# nixieklok.net
KiCad netlist of a schematic drawn in Altium Designer
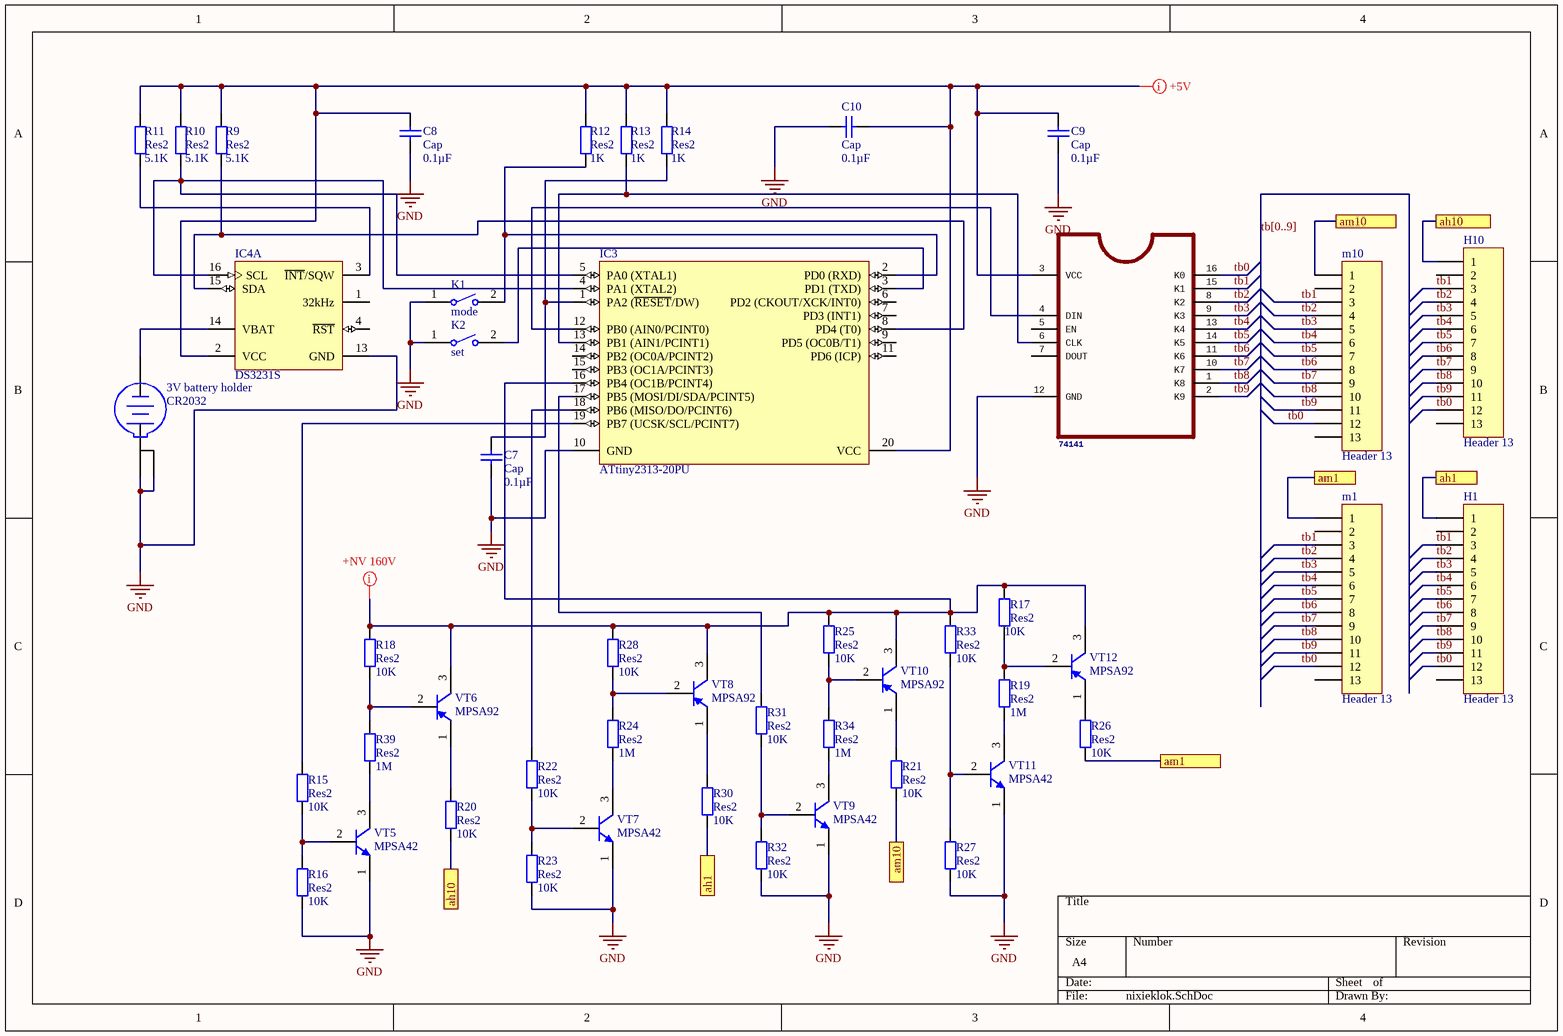
[diagram p0: nixieklok.SchDoc]

(export (version "E")
  (design (tool "Eeschema 10.0.6"))
  (components
    (comp (ref "3V battery holder")
      (value "CR2032")
      (footprint "RENA-HU2032-LF_V")
      (description "Coin Cell Battery Holder, CR2032, Horizontal, -40 to 100 degC, 3-Pin THD, RoHS, Tray")
      (fields (field (name "MANUFACTURER") "Renata"))
      (libsource (lib "Altium Content Vault") (part "BATTERY-HOLDER-COIN-3"))
    )
    (comp (ref "74141")
      (value "NIXIE_DRIVER_V1")
      (footprint "DIP-16")
      (fields (field (name "LIBRARYNAME") "Nixie_Tube_Driver_Altium_Library"))
      (libsource (lib "Nixie_Tube_Driver_Altium_Library") (part "NIXIE_DRIVER_V1"))
    )
    (comp (ref "C7")
      (value "Cap")
      (footprint "RAD-0.3")
      (description "Capacitor")
      (fields (field (name "ALTIUM_VALUE") "0.1µF") (field (name "PUBLISHER") "Altium Limited"))
      (libsource (lib "Miscellaneous Devices") (part "Cap"))
    )
    (comp (ref "C8")
      (value "Cap")
      (footprint "RAD-0.3")
      (description "Capacitor")
      (fields (field (name "ALTIUM_VALUE") "0.1µF") (field (name "PUBLISHER") "Altium Limited"))
      (libsource (lib "Miscellaneous Devices") (part "Cap"))
    )
    (comp (ref "C9")
      (value "Cap")
      (footprint "RAD-0.3")
      (description "Capacitor")
      (fields (field (name "ALTIUM_VALUE") "0.1µF") (field (name "PUBLISHER") "Altium Limited"))
      (libsource (lib "Miscellaneous Devices") (part "Cap"))
    )
    (comp (ref "C10")
      (value "Cap")
      (footprint "RAD-0.3")
      (description "Capacitor")
      (fields (field (name "ALTIUM_VALUE") "0.1µF") (field (name "PUBLISHER") "Altium Limited"))
      (libsource (lib "Miscellaneous Devices") (part "Cap"))
    )
    (comp (ref "H1")
      (value "Header 13")
      (footprint "HDR1X13")
      (description "Header, 13-Pin")
      (fields (field (name "PUBLISHER") "Altium Limited"))
      (libsource (lib "Miscellaneous Connectors") (part "Header 13"))
    )
    (comp (ref "H10")
      (value "Header 13")
      (footprint "HDR1X13")
      (description "Header, 13-Pin")
      (fields (field (name "PUBLISHER") "Altium Limited"))
      (libsource (lib "Miscellaneous Connectors") (part "Header 13"))
    )
    (comp (ref "IC3")
      (value "ATtiny2313-20PU")
      (footprint "20P3")
      (libsource (lib "Altium Content Vault") (part "MC-8B-ATT2313-IL20"))
    )
    (comp (ref "IC4")
      (value "DS3231S")
      (footprint "W16-H2_L")
      (description "Extremely Accurate I2C-Integrated Real-Time Clock/TCXO/Crystal, 16-Pin SO, 0 to 70 degC")
      (libsource (lib "Altium Content Vault") (part "MAX-RTC-16-DS3231S-W16#H2"))
    )
    (comp (ref "K1")
      (value "mode")
      (footprint "TECO-FSMSM-2_V")
      (description "FSMSM Push Button Switch, 50 mA, -35 to 85 degC, 2-Pin SMD, RoHS, Bulk")
      (fields (field (name "MANUFACTURER") "TE Connectivity"))
      (libsource (lib "Altium Content Vault") (part "SW-SPST-2_C"))
    )
    (comp (ref "K2")
      (value "set")
      (footprint "TECO-FSMSM-2_V")
      (description "FSMSM Push Button Switch, 50 mA, -35 to 85 degC, 2-Pin SMD, RoHS, Bulk")
      (fields (field (name "MANUFACTURER") "TE Connectivity"))
      (libsource (lib "Altium Content Vault") (part "SW-SPST-2_C"))
    )
    (comp (ref "m1")
      (value "Header 13")
      (footprint "HDR1X13")
      (description "Header, 13-Pin")
      (fields (field (name "PUBLISHER") "Altium Limited"))
      (libsource (lib "Miscellaneous Connectors") (part "Header 13"))
    )
    (comp (ref "m10")
      (value "Header 13")
      (footprint "HDR1X13")
      (description "Header, 13-Pin")
      (fields (field (name "PUBLISHER") "Altium Limited"))
      (libsource (lib "Miscellaneous Connectors") (part "Header 13"))
    )
    (comp (ref "R9")
      (value "Res2")
      (footprint "AXIAL-0.4")
      (description "Resistor")
      (fields (field (name "ALTIUM_VALUE") "5.1K") (field (name "PUBLISHER") "Altium Limited"))
      (libsource (lib "Miscellaneous Devices") (part "Res2"))
    )
    (comp (ref "R10")
      (value "Res2")
      (footprint "AXIAL-0.4")
      (description "Resistor")
      (fields (field (name "ALTIUM_VALUE") "5.1K") (field (name "PUBLISHER") "Altium Limited"))
      (libsource (lib "Miscellaneous Devices") (part "Res2"))
    )
    (comp (ref "R11")
      (value "Res2")
      (footprint "AXIAL-0.4")
      (description "Resistor")
      (fields (field (name "ALTIUM_VALUE") "5.1K") (field (name "PUBLISHER") "Altium Limited"))
      (libsource (lib "Miscellaneous Devices") (part "Res2"))
    )
    (comp (ref "R12")
      (value "Res2")
      (footprint "AXIAL-0.4")
      (description "Resistor")
      (fields (field (name "ALTIUM_VALUE") "1K") (field (name "PUBLISHER") "Altium Limited"))
      (libsource (lib "Miscellaneous Devices") (part "Res2"))
    )
    (comp (ref "R13")
      (value "Res2")
      (footprint "AXIAL-0.4")
      (description "Resistor")
      (fields (field (name "ALTIUM_VALUE") "1K") (field (name "PUBLISHER") "Altium Limited"))
      (libsource (lib "Miscellaneous Devices") (part "Res2"))
    )
    (comp (ref "R14")
      (value "Res2")
      (footprint "AXIAL-0.4")
      (description "Resistor")
      (fields (field (name "ALTIUM_VALUE") "1K") (field (name "PUBLISHER") "Altium Limited"))
      (libsource (lib "Miscellaneous Devices") (part "Res2"))
    )
    (comp (ref "R15")
      (value "Res2")
      (footprint "AXIAL-0.4")
      (description "Resistor")
      (fields (field (name "ALTIUM_VALUE") "10K") (field (name "PUBLISHER") "Altium Limited"))
      (libsource (lib "Miscellaneous Devices") (part "Res2"))
    )
    (comp (ref "R16")
      (value "Res2")
      (footprint "AXIAL-0.4")
      (description "Resistor")
      (fields (field (name "ALTIUM_VALUE") "10K") (field (name "PUBLISHER") "Altium Limited"))
      (libsource (lib "Miscellaneous Devices") (part "Res2"))
    )
    (comp (ref "R17")
      (value "Res2")
      (footprint "AXIAL-0.4")
      (description "Resistor")
      (fields (field (name "ALTIUM_VALUE") "10K") (field (name "PUBLISHER") "Altium Limited"))
      (libsource (lib "Miscellaneous Devices") (part "Res2"))
    )
    (comp (ref "R18")
      (value "Res2")
      (footprint "AXIAL-0.4")
      (description "Resistor")
      (fields (field (name "ALTIUM_VALUE") "10K") (field (name "PUBLISHER") "Altium Limited"))
      (libsource (lib "Miscellaneous Devices") (part "Res2"))
    )
    (comp (ref "R19")
      (value "Res2")
      (footprint "AXIAL-0.4")
      (description "Resistor")
      (fields (field (name "ALTIUM_VALUE") "1M") (field (name "PUBLISHER") "Altium Limited"))
      (libsource (lib "Miscellaneous Devices") (part "Res2"))
    )
    (comp (ref "R20")
      (value "Res2")
      (footprint "AXIAL-0.4")
      (description "Resistor")
      (fields (field (name "ALTIUM_VALUE") "10K") (field (name "PUBLISHER") "Altium Limited"))
      (libsource (lib "Miscellaneous Devices") (part "Res2"))
    )
    (comp (ref "R21")
      (value "Res2")
      (footprint "AXIAL-0.4")
      (description "Resistor")
      (fields (field (name "ALTIUM_VALUE") "10K") (field (name "PUBLISHER") "Altium Limited"))
      (libsource (lib "Miscellaneous Devices") (part "Res2"))
    )
    (comp (ref "R22")
      (value "Res2")
      (footprint "AXIAL-0.4")
      (description "Resistor")
      (fields (field (name "ALTIUM_VALUE") "10K") (field (name "PUBLISHER") "Altium Limited"))
      (libsource (lib "Miscellaneous Devices") (part "Res2"))
    )
    (comp (ref "R23")
      (value "Res2")
      (footprint "AXIAL-0.4")
      (description "Resistor")
      (fields (field (name "ALTIUM_VALUE") "10K") (field (name "PUBLISHER") "Altium Limited"))
      (libsource (lib "Miscellaneous Devices") (part "Res2"))
    )
    (comp (ref "R24")
      (value "Res2")
      (footprint "AXIAL-0.4")
      (description "Resistor")
      (fields (field (name "ALTIUM_VALUE") "1M") (field (name "PUBLISHER") "Altium Limited"))
      (libsource (lib "Miscellaneous Devices") (part "Res2"))
    )
    (comp (ref "R25")
      (value "Res2")
      (footprint "AXIAL-0.4")
      (description "Resistor")
      (fields (field (name "ALTIUM_VALUE") "10K") (field (name "PUBLISHER") "Altium Limited"))
      (libsource (lib "Miscellaneous Devices") (part "Res2"))
    )
    (comp (ref "R26")
      (value "Res2")
      (footprint "AXIAL-0.4")
      (description "Resistor")
      (fields (field (name "ALTIUM_VALUE") "10K") (field (name "PUBLISHER") "Altium Limited"))
      (libsource (lib "Miscellaneous Devices") (part "Res2"))
    )
    (comp (ref "R27")
      (value "Res2")
      (footprint "AXIAL-0.4")
      (description "Resistor")
      (fields (field (name "ALTIUM_VALUE") "10K") (field (name "PUBLISHER") "Altium Limited"))
      (libsource (lib "Miscellaneous Devices") (part "Res2"))
    )
    (comp (ref "R28")
      (value "Res2")
      (footprint "AXIAL-0.4")
      (description "Resistor")
      (fields (field (name "ALTIUM_VALUE") "10K") (field (name "PUBLISHER") "Altium Limited"))
      (libsource (lib "Miscellaneous Devices") (part "Res2"))
    )
    (comp (ref "R30")
      (value "Res2")
      (footprint "AXIAL-0.4")
      (description "Resistor")
      (fields (field (name "ALTIUM_VALUE") "10K") (field (name "PUBLISHER") "Altium Limited"))
      (libsource (lib "Miscellaneous Devices") (part "Res2"))
    )
    (comp (ref "R31")
      (value "Res2")
      (footprint "AXIAL-0.4")
      (description "Resistor")
      (fields (field (name "ALTIUM_VALUE") "10K") (field (name "PUBLISHER") "Altium Limited"))
      (libsource (lib "Miscellaneous Devices") (part "Res2"))
    )
    (comp (ref "R32")
      (value "Res2")
      (footprint "AXIAL-0.4")
      (description "Resistor")
      (fields (field (name "ALTIUM_VALUE") "10K") (field (name "PUBLISHER") "Altium Limited"))
      (libsource (lib "Miscellaneous Devices") (part "Res2"))
    )
    (comp (ref "R33")
      (value "Res2")
      (footprint "AXIAL-0.4")
      (description "Resistor")
      (fields (field (name "ALTIUM_VALUE") "10K") (field (name "PUBLISHER") "Altium Limited"))
      (libsource (lib "Miscellaneous Devices") (part "Res2"))
    )
    (comp (ref "R34")
      (value "Res2")
      (footprint "AXIAL-0.4")
      (description "Resistor")
      (fields (field (name "ALTIUM_VALUE") "1M") (field (name "PUBLISHER") "Altium Limited"))
      (libsource (lib "Miscellaneous Devices") (part "Res2"))
    )
    (comp (ref "R39")
      (value "Res2")
      (footprint "AXIAL-0.4")
      (description "Resistor")
      (fields (field (name "ALTIUM_VALUE") "1M") (field (name "PUBLISHER") "Altium Limited"))
      (libsource (lib "Miscellaneous Devices") (part "Res2"))
    )
    (comp (ref "VT5")
      (value "MPSA42")
      (footprint "ONSC-TO-92-3-29-11")
      (description "High Voltage Transistor, NPN Silicon, 3-Pin TO-92, Bulk Box")
      (fields (field (name "MANUFACTURER") "On Semiconductor"))
      (libsource (lib "Altium Content Vault") (part "ONSC-NPN-E1B2C3-3"))
    )
    (comp (ref "VT6")
      (value "MPSA92")
      (footprint "ONSC-TO-92-3-29-11")
      (description "High Voltage Transistor, PNP Silicon, 3-Pin TO-92, Bulk Box")
      (fields (field (name "MANUFACTURER") "On Semiconductor"))
      (libsource (lib "Altium Content Vault") (part "ONSC-PNP-E1B2C3-3"))
    )
    (comp (ref "VT7")
      (value "MPSA42")
      (footprint "ONSC-TO-92-3-29-11")
      (description "High Voltage Transistor, NPN Silicon, 3-Pin TO-92, Bulk Box")
      (fields (field (name "MANUFACTURER") "On Semiconductor"))
      (libsource (lib "Altium Content Vault") (part "ONSC-NPN-E1B2C3-3"))
    )
    (comp (ref "VT8")
      (value "MPSA92")
      (footprint "ONSC-TO-92-3-29-11")
      (description "High Voltage Transistor, PNP Silicon, 3-Pin TO-92, Bulk Box")
      (fields (field (name "MANUFACTURER") "On Semiconductor"))
      (libsource (lib "Altium Content Vault") (part "ONSC-PNP-E1B2C3-3"))
    )
    (comp (ref "VT9")
      (value "MPSA42")
      (footprint "ONSC-TO-92-3-29-11")
      (description "High Voltage Transistor, NPN Silicon, 3-Pin TO-92, Bulk Box")
      (fields (field (name "MANUFACTURER") "On Semiconductor"))
      (libsource (lib "Altium Content Vault") (part "ONSC-NPN-E1B2C3-3"))
    )
    (comp (ref "VT10")
      (value "MPSA92")
      (footprint "ONSC-TO-92-3-29-11")
      (description "High Voltage Transistor, PNP Silicon, 3-Pin TO-92, Bulk Box")
      (fields (field (name "MANUFACTURER") "On Semiconductor"))
      (libsource (lib "Altium Content Vault") (part "ONSC-PNP-E1B2C3-3"))
    )
    (comp (ref "VT11")
      (value "MPSA42")
      (footprint "ONSC-TO-92-3-29-11")
      (description "High Voltage Transistor, NPN Silicon, 3-Pin TO-92, Bulk Box")
      (fields (field (name "MANUFACTURER") "On Semiconductor"))
      (libsource (lib "Altium Content Vault") (part "ONSC-NPN-E1B2C3-3"))
    )
    (comp (ref "VT12")
      (value "MPSA92")
      (footprint "ONSC-TO-92-3-29-11")
      (description "High Voltage Transistor, PNP Silicon, 3-Pin TO-92, Bulk Box")
      (fields (field (name "MANUFACTURER") "On Semiconductor"))
      (libsource (lib "Altium Content Vault") (part "ONSC-PNP-E1B2C3-3"))
    )
  )
  (nets
    (net (code "1") (name "/ah1") (class "Default")
      (node (ref "H1") (pin "1") (pinfunction "1_1") (pintype "passive"))
      (node (ref "R30") (pin "1") (pinfunction "1_1") (pintype "passive"))
    )
    (net (code "2") (name "/ah10") (class "Default")
      (node (ref "H10") (pin "1") (pinfunction "1_1") (pintype "passive"))
      (node (ref "R20") (pin "1") (pinfunction "1_1") (pintype "passive"))
    )
    (net (code "3") (name "/am1") (class "Default")
      (node (ref "R26") (pin "1") (pinfunction "1_1") (pintype "passive"))
      (node (ref "m1") (pin "1") (pinfunction "1_1") (pintype "passive"))
    )
    (net (code "4") (name "/am10") (class "Default")
      (node (ref "R21") (pin "1") (pinfunction "1_1") (pintype "passive"))
      (node (ref "m10") (pin "1") (pinfunction "1_1") (pintype "passive"))
    )
    (net (code "5") (name "/tb0") (class "Default")
      (node (ref "74141") (pin "16") (pinfunction "K0_16") (pintype "passive"))
      (node (ref "H1") (pin "12") (pinfunction "12_12") (pintype "passive"))
      (node (ref "H10") (pin "12") (pinfunction "12_12") (pintype "passive"))
      (node (ref "m1") (pin "12") (pinfunction "12_12") (pintype "passive"))
      (node (ref "m10") (pin "12") (pinfunction "12_12") (pintype "passive"))
    )
    (net (code "6") (name "/tb1") (class "Default")
      (node (ref "74141") (pin "15") (pinfunction "K1_15") (pintype "passive"))
      (node (ref "H1") (pin "3") (pinfunction "3_3") (pintype "passive"))
      (node (ref "H10") (pin "3") (pinfunction "3_3") (pintype "passive"))
      (node (ref "m1") (pin "3") (pinfunction "3_3") (pintype "passive"))
      (node (ref "m10") (pin "3") (pinfunction "3_3") (pintype "passive"))
    )
    (net (code "7") (name "/tb2") (class "Default")
      (node (ref "74141") (pin "8") (pinfunction "K2_8") (pintype "passive"))
      (node (ref "H1") (pin "4") (pinfunction "4_4") (pintype "passive"))
      (node (ref "H10") (pin "4") (pinfunction "4_4") (pintype "passive"))
      (node (ref "m1") (pin "4") (pinfunction "4_4") (pintype "passive"))
      (node (ref "m10") (pin "4") (pinfunction "4_4") (pintype "passive"))
    )
    (net (code "8") (name "/tb3") (class "Default")
      (node (ref "74141") (pin "9") (pinfunction "K3_9") (pintype "passive"))
      (node (ref "H1") (pin "5") (pinfunction "5_5") (pintype "passive"))
      (node (ref "H10") (pin "5") (pinfunction "5_5") (pintype "passive"))
      (node (ref "m1") (pin "5") (pinfunction "5_5") (pintype "passive"))
      (node (ref "m10") (pin "5") (pinfunction "5_5") (pintype "passive"))
    )
    (net (code "9") (name "/tb4") (class "Default")
      (node (ref "74141") (pin "13") (pinfunction "K4_13") (pintype "passive"))
      (node (ref "H1") (pin "6") (pinfunction "6_6") (pintype "passive"))
      (node (ref "H10") (pin "6") (pinfunction "6_6") (pintype "passive"))
      (node (ref "m1") (pin "6") (pinfunction "6_6") (pintype "passive"))
      (node (ref "m10") (pin "6") (pinfunction "6_6") (pintype "passive"))
    )
    (net (code "10") (name "/tb5") (class "Default")
      (node (ref "74141") (pin "14") (pinfunction "K5_14") (pintype "passive"))
      (node (ref "H1") (pin "7") (pinfunction "7_7") (pintype "passive"))
      (node (ref "H10") (pin "7") (pinfunction "7_7") (pintype "passive"))
      (node (ref "m1") (pin "7") (pinfunction "7_7") (pintype "passive"))
      (node (ref "m10") (pin "7") (pinfunction "7_7") (pintype "passive"))
    )
    (net (code "11") (name "/tb6") (class "Default")
      (node (ref "74141") (pin "11") (pinfunction "K6_11") (pintype "passive"))
      (node (ref "H1") (pin "8") (pinfunction "8_8") (pintype "passive"))
      (node (ref "H10") (pin "8") (pinfunction "8_8") (pintype "passive"))
      (node (ref "m1") (pin "8") (pinfunction "8_8") (pintype "passive"))
      (node (ref "m10") (pin "8") (pinfunction "8_8") (pintype "passive"))
    )
    (net (code "12") (name "/tb7") (class "Default")
      (node (ref "74141") (pin "10") (pinfunction "K7_10") (pintype "passive"))
      (node (ref "H1") (pin "9") (pinfunction "9_9") (pintype "passive"))
      (node (ref "H10") (pin "9") (pinfunction "9_9") (pintype "passive"))
      (node (ref "m1") (pin "9") (pinfunction "9_9") (pintype "passive"))
      (node (ref "m10") (pin "9") (pinfunction "9_9") (pintype "passive"))
    )
    (net (code "13") (name "/tb8") (class "Default")
      (node (ref "74141") (pin "1") (pinfunction "K8_1") (pintype "passive"))
      (node (ref "H1") (pin "10") (pinfunction "10_10") (pintype "passive"))
      (node (ref "H10") (pin "10") (pinfunction "10_10") (pintype "passive"))
      (node (ref "m1") (pin "10") (pinfunction "10_10") (pintype "passive"))
      (node (ref "m10") (pin "10") (pinfunction "10_10") (pintype "passive"))
    )
    (net (code "14") (name "/tb9") (class "Default")
      (node (ref "74141") (pin "2") (pinfunction "K9_2") (pintype "passive"))
      (node (ref "H1") (pin "11") (pinfunction "11_11") (pintype "passive"))
      (node (ref "H10") (pin "11") (pinfunction "11_11") (pintype "passive"))
      (node (ref "m1") (pin "11") (pinfunction "11_11") (pintype "passive"))
      (node (ref "m10") (pin "11") (pinfunction "11_11") (pintype "passive"))
    )
    (net (code "16") (name "GND") (class "Default")
      (node (ref "3V battery holder") (pin "1") (pinfunction "+_1") (pintype "passive"))
      (node (ref "3V battery holder") (pin "2") (pinfunction "+_2") (pintype "passive"))
      (node (ref "74141") (pin "12") (pinfunction "GND_12") (pintype "power_in"))
      (node (ref "C10") (pin "1") (pinfunction "1_1") (pintype "passive"))
      (node (ref "C7") (pin "1") (pinfunction "1_1") (pintype "passive"))
      (node (ref "C8") (pin "1") (pinfunction "1_1") (pintype "passive"))
      (node (ref "C9") (pin "1") (pinfunction "1_1") (pintype "passive"))
      (node (ref "IC3") (pin "10") (pinfunction "GND_10") (pintype "power_in"))
      (node (ref "IC4") (pin "13") (pinfunction "GND_13") (pintype "power_in"))
      (node (ref "K1") (pin "1") (pinfunction "1_1") (pintype "passive"))
      (node (ref "K2") (pin "1") (pinfunction "1_1") (pintype "passive"))
      (node (ref "R16") (pin "1") (pinfunction "1_1") (pintype "passive"))
      (node (ref "R23") (pin "1") (pinfunction "1_1") (pintype "passive"))
      (node (ref "R27") (pin "1") (pinfunction "1_1") (pintype "passive"))
      (node (ref "R32") (pin "1") (pinfunction "1_1") (pintype "passive"))
      (node (ref "VT11") (pin "1") (pinfunction "E_1") (pintype "passive"))
      (node (ref "VT5") (pin "1") (pinfunction "E_1") (pintype "passive"))
      (node (ref "VT7") (pin "1") (pinfunction "E_1") (pintype "passive"))
      (node (ref "VT9") (pin "1") (pinfunction "E_1") (pintype "passive"))
    )
    (net (code "17") (name "Net-(3V battery holder--)") (class "Default")
      (node (ref "3V battery holder") (pin "3") (pinfunction "-_3") (pintype "passive"))
      (node (ref "IC4") (pin "14") (pinfunction "VBAT_14") (pintype "power_in"))
    )
    (net (code "18") (name "Net-(74141-CLK)") (class "Default")
      (node (ref "74141") (pin "6") (pinfunction "CLK_6") (pintype "passive"))
      (node (ref "IC3") (pin "13") (pinfunction "PB1_(AIN1/PCINT1)_13") (pintype "bidirectional"))
      (node (ref "R13") (pin "1") (pinfunction "1_1") (pintype "passive"))
    )
    (net (code "19") (name "Net-(74141-DIN)") (class "Default")
      (node (ref "74141") (pin "4") (pinfunction "DIN_4") (pintype "passive"))
      (node (ref "IC3") (pin "12") (pinfunction "PB0_(AIN0/PCINT0)_12") (pintype "bidirectional"))
    )
    (net (code "20") (name "Net-(74141-VCC)") (class "Default")
      (node (ref "74141") (pin "3") (pinfunction "VCC_3") (pintype "power_in"))
      (node (ref "C10") (pin "2") (pinfunction "2_2") (pintype "passive"))
      (node (ref "C8") (pin "2") (pinfunction "2_2") (pintype "passive"))
      (node (ref "C9") (pin "2") (pinfunction "2_2") (pintype "passive"))
      (node (ref "IC3") (pin "20") (pinfunction "VCC_20") (pintype "power_in"))
      (node (ref "IC4") (pin "2") (pinfunction "VCC_2") (pintype "power_in"))
      (node (ref "R10") (pin "2") (pinfunction "2_2") (pintype "passive"))
      (node (ref "R11") (pin "2") (pinfunction "2_2") (pintype "passive"))
      (node (ref "R12") (pin "2") (pinfunction "2_2") (pintype "passive"))
      (node (ref "R13") (pin "2") (pinfunction "2_2") (pintype "passive"))
      (node (ref "R14") (pin "2") (pinfunction "2_2") (pintype "passive"))
      (node (ref "R9") (pin "2") (pinfunction "2_2") (pintype "passive"))
    )
    (net (code "21") (name "Net-(IC3-PA0_(XTAL1))") (class "Default")
      (node (ref "IC3") (pin "4") (pinfunction "PA1_(XTAL2)_4") (pintype "bidirectional"))
      (node (ref "IC3") (pin "5") (pinfunction "PA0_(XTAL1)_5") (pintype "bidirectional"))
      (node (ref "IC4") (pin "16") (pinfunction "SCL_16") (pintype "input"))
      (node (ref "R10") (pin "1") (pinfunction "1_1") (pintype "passive"))
    )
    (net (code "22") (name "Net-(IC3-PA2_(~{RESET}{slash}DW))") (class "Default")
      (node (ref "C7") (pin "2") (pinfunction "2_2") (pintype "passive"))
      (node (ref "IC3") (pin "1") (pinfunction "PA2_(~{RESET}/DW)_1") (pintype "bidirectional"))
      (node (ref "R14") (pin "1") (pinfunction "1_1") (pintype "passive"))
    )
    (net (code "23") (name "Net-(IC3-PB4_(OC1B{slash}PCINT4))") (class "Default")
      (node (ref "IC3") (pin "16") (pinfunction "PB4_(OC1B/PCINT4)_16") (pintype "bidirectional"))
      (node (ref "R17") (pin "2") (pinfunction "2_2") (pintype "passive"))
      (node (ref "R18") (pin "2") (pinfunction "2_2") (pintype "passive"))
      (node (ref "R25") (pin "2") (pinfunction "2_2") (pintype "passive"))
      (node (ref "R28") (pin "2") (pinfunction "2_2") (pintype "passive"))
      (node (ref "R33") (pin "2") (pinfunction "2_2") (pintype "passive"))
      (node (ref "VT10") (pin "3") (pinfunction "C_3") (pintype "passive"))
      (node (ref "VT12") (pin "3") (pinfunction "C_3") (pintype "passive"))
      (node (ref "VT6") (pin "3") (pinfunction "C_3") (pintype "passive"))
      (node (ref "VT8") (pin "3") (pinfunction "C_3") (pintype "passive"))
    )
    (net (code "24") (name "Net-(IC3-PB5_(MOSI{slash}DI{slash}SDA{slash}PCINT5))") (class "Default")
      (node (ref "IC3") (pin "17") (pinfunction "PB5_(MOSI/DI/SDA/PCINT5)_17") (pintype "bidirectional"))
      (node (ref "R31") (pin "2") (pinfunction "2_2") (pintype "passive"))
    )
    (net (code "25") (name "Net-(IC3-PB6_(MISO{slash}DO{slash}PCINT6))") (class "Default")
      (node (ref "IC3") (pin "18") (pinfunction "PB6_(MISO/DO/PCINT6)_18") (pintype "bidirectional"))
      (node (ref "R22") (pin "2") (pinfunction "2_2") (pintype "passive"))
    )
    (net (code "26") (name "Net-(IC3-PB7_(UCSK{slash}SCL{slash}PCINT7))") (class "Default")
      (node (ref "IC3") (pin "19") (pinfunction "PB7_(UCSK/SCL/PCINT7)_19") (pintype "bidirectional"))
      (node (ref "R15") (pin "2") (pinfunction "2_2") (pintype "passive"))
    )
    (net (code "27") (name "Net-(IC3-PD0_(RXD))") (class "Default")
      (node (ref "IC3") (pin "2") (pinfunction "PD0_(RXD)_2") (pintype "bidirectional"))
      (node (ref "K1") (pin "2") (pinfunction "2_2") (pintype "passive"))
      (node (ref "R12") (pin "1") (pinfunction "1_1") (pintype "passive"))
    )
    (net (code "28") (name "Net-(IC3-PD1_(TXD))") (class "Default")
      (node (ref "IC3") (pin "3") (pinfunction "PD1_(TXD)_3") (pintype "bidirectional"))
      (node (ref "K2") (pin "2") (pinfunction "2_2") (pintype "passive"))
    )
    (net (code "29") (name "Net-(IC3-PD4_(T0))") (class "Default")
      (node (ref "IC3") (pin "8") (pinfunction "PD4_(T0)_8") (pintype "bidirectional"))
      (node (ref "IC4") (pin "15") (pinfunction "SDA_15") (pintype "bidirectional"))
      (node (ref "R9") (pin "1") (pinfunction "1_1") (pintype "passive"))
    )
    (net (code "30") (name "Net-(IC4A-~{INT}{slash}SQW)") (class "Default")
      (node (ref "IC4") (pin "3") (pinfunction "~{INT}/SQW_3") (pintype "open_collector"))
      (node (ref "R11") (pin "1") (pinfunction "1_1") (pintype "passive"))
    )
    (net (code "31") (name "Net-(VT5-B)") (class "Default")
      (node (ref "R15") (pin "1") (pinfunction "1_1") (pintype "passive"))
      (node (ref "R16") (pin "2") (pinfunction "2_2") (pintype "passive"))
      (node (ref "VT5") (pin "2") (pinfunction "B_2") (pintype "passive"))
    )
    (net (code "32") (name "Net-(VT5-C)") (class "Default")
      (node (ref "R39") (pin "1") (pinfunction "1_1") (pintype "passive"))
      (node (ref "VT5") (pin "3") (pinfunction "C_3") (pintype "passive"))
    )
    (net (code "33") (name "Net-(VT6-B)") (class "Default")
      (node (ref "R18") (pin "1") (pinfunction "1_1") (pintype "passive"))
      (node (ref "R39") (pin "2") (pinfunction "2_2") (pintype "passive"))
      (node (ref "VT6") (pin "2") (pinfunction "B_2") (pintype "passive"))
    )
    (net (code "34") (name "Net-(VT6-E)") (class "Default")
      (node (ref "R20") (pin "2") (pinfunction "2_2") (pintype "passive"))
      (node (ref "VT6") (pin "1") (pinfunction "E_1") (pintype "passive"))
    )
    (net (code "35") (name "Net-(VT7-B)") (class "Default")
      (node (ref "R22") (pin "1") (pinfunction "1_1") (pintype "passive"))
      (node (ref "R23") (pin "2") (pinfunction "2_2") (pintype "passive"))
      (node (ref "VT7") (pin "2") (pinfunction "B_2") (pintype "passive"))
    )
    (net (code "36") (name "Net-(VT7-C)") (class "Default")
      (node (ref "R24") (pin "1") (pinfunction "1_1") (pintype "passive"))
      (node (ref "VT7") (pin "3") (pinfunction "C_3") (pintype "passive"))
    )
    (net (code "37") (name "Net-(VT8-B)") (class "Default")
      (node (ref "R24") (pin "2") (pinfunction "2_2") (pintype "passive"))
      (node (ref "R28") (pin "1") (pinfunction "1_1") (pintype "passive"))
      (node (ref "VT8") (pin "2") (pinfunction "B_2") (pintype "passive"))
    )
    (net (code "38") (name "Net-(VT8-E)") (class "Default")
      (node (ref "R30") (pin "2") (pinfunction "2_2") (pintype "passive"))
      (node (ref "VT8") (pin "1") (pinfunction "E_1") (pintype "passive"))
    )
    (net (code "39") (name "Net-(VT9-B)") (class "Default")
      (node (ref "R31") (pin "1") (pinfunction "1_1") (pintype "passive"))
      (node (ref "R32") (pin "2") (pinfunction "2_2") (pintype "passive"))
      (node (ref "VT9") (pin "2") (pinfunction "B_2") (pintype "passive"))
    )
    (net (code "40") (name "Net-(VT9-C)") (class "Default")
      (node (ref "R34") (pin "1") (pinfunction "1_1") (pintype "passive"))
      (node (ref "VT9") (pin "3") (pinfunction "C_3") (pintype "passive"))
    )
    (net (code "41") (name "Net-(VT10-B)") (class "Default")
      (node (ref "R25") (pin "1") (pinfunction "1_1") (pintype "passive"))
      (node (ref "R34") (pin "2") (pinfunction "2_2") (pintype "passive"))
      (node (ref "VT10") (pin "2") (pinfunction "B_2") (pintype "passive"))
    )
    (net (code "42") (name "Net-(VT10-E)") (class "Default")
      (node (ref "R21") (pin "2") (pinfunction "2_2") (pintype "passive"))
      (node (ref "VT10") (pin "1") (pinfunction "E_1") (pintype "passive"))
    )
    (net (code "43") (name "Net-(VT11-B)") (class "Default")
      (node (ref "R27") (pin "2") (pinfunction "2_2") (pintype "passive"))
      (node (ref "R33") (pin "1") (pinfunction "1_1") (pintype "passive"))
      (node (ref "VT11") (pin "2") (pinfunction "B_2") (pintype "passive"))
    )
    (net (code "44") (name "Net-(VT11-C)") (class "Default")
      (node (ref "R19") (pin "1") (pinfunction "1_1") (pintype "passive"))
      (node (ref "VT11") (pin "3") (pinfunction "C_3") (pintype "passive"))
    )
    (net (code "45") (name "Net-(VT12-B)") (class "Default")
      (node (ref "R17") (pin "1") (pinfunction "1_1") (pintype "passive"))
      (node (ref "R19") (pin "2") (pinfunction "2_2") (pintype "passive"))
      (node (ref "VT12") (pin "2") (pinfunction "B_2") (pintype "passive"))
    )
    (net (code "46") (name "Net-(VT12-E)") (class "Default")
      (node (ref "R26") (pin "2") (pinfunction "2_2") (pintype "passive"))
      (node (ref "VT12") (pin "1") (pinfunction "E_1") (pintype "passive"))
    )
    (net (code "47") (name "unconnected-(74141-DOUT-Pad7)") (class "Default")
      (node (ref "74141") (pin "7") (pinfunction "DOUT_7") (pintype "passive"))
    )
    (net (code "48") (name "unconnected-(74141-EN-Pad5)") (class "Default")
      (node (ref "74141") (pin "5") (pinfunction "EN_5") (pintype "passive"))
    )
    (net (code "49") (name "unconnected-(H1-Pad2)") (class "Default")
      (node (ref "H1") (pin "2") (pinfunction "2_2") (pintype "passive"))
    )
    (net (code "50") (name "unconnected-(H1-Pad13)") (class "Default")
      (node (ref "H1") (pin "13") (pinfunction "13_13") (pintype "passive"))
    )
    (net (code "51") (name "unconnected-(H10-Pad2)") (class "Default")
      (node (ref "H10") (pin "2") (pinfunction "2_2") (pintype "passive"))
    )
    (net (code "52") (name "unconnected-(H10-Pad13)") (class "Default")
      (node (ref "H10") (pin "13") (pinfunction "13_13") (pintype "passive"))
    )
    (net (code "53") (name "unconnected-(IC3-PB2_(OC0A{slash}PCINT2)-Pad14)") (class "Default")
      (node (ref "IC3") (pin "14") (pinfunction "PB2_(OC0A/PCINT2)_14") (pintype "bidirectional"))
    )
    (net (code "54") (name "unconnected-(IC3-PB3_(OC1A{slash}PCINT3)-Pad15)") (class "Default")
      (node (ref "IC3") (pin "15") (pinfunction "PB3_(OC1A/PCINT3)_15") (pintype "bidirectional"))
    )
    (net (code "55") (name "unconnected-(IC3-PD2_(CKOUT{slash}XCK{slash}INT0)-Pad6)") (class "Default")
      (node (ref "IC3") (pin "6") (pinfunction "PD2_(CKOUT/XCK/INT0)_6") (pintype "bidirectional"))
    )
    (net (code "56") (name "unconnected-(IC3-PD3_(INT1)-Pad7)") (class "Default")
      (node (ref "IC3") (pin "7") (pinfunction "PD3_(INT1)_7") (pintype "bidirectional"))
    )
    (net (code "57") (name "unconnected-(IC3-PD5_(OC0B{slash}T1)-Pad9)") (class "Default")
      (node (ref "IC3") (pin "9") (pinfunction "PD5_(OC0B/T1)_9") (pintype "bidirectional"))
    )
    (net (code "58") (name "unconnected-(IC3-PD6_(ICP)-Pad11)") (class "Default")
      (node (ref "IC3") (pin "11") (pinfunction "PD6_(ICP)_11") (pintype "bidirectional"))
    )
    (net (code "59") (name "unconnected-(IC4A-32kHz-Pad1)") (class "Default")
      (node (ref "IC4") (pin "1") (pinfunction "32kHz_1") (pintype "open_collector"))
    )
    (net (code "60") (name "unconnected-(IC4A-~{RST}-Pad4)") (class "Default")
      (node (ref "IC4") (pin "4") (pinfunction "~{RST}_4") (pintype "bidirectional"))
    )
    (net (code "61") (name "unconnected-(m1-Pad2)") (class "Default")
      (node (ref "m1") (pin "2") (pinfunction "2_2") (pintype "passive"))
    )
    (net (code "62") (name "unconnected-(m1-Pad13)") (class "Default")
      (node (ref "m1") (pin "13") (pinfunction "13_13") (pintype "passive"))
    )
    (net (code "63") (name "unconnected-(m10-Pad2)") (class "Default")
      (node (ref "m10") (pin "2") (pinfunction "2_2") (pintype "passive"))
    )
    (net (code "64") (name "unconnected-(m10-Pad13)") (class "Default")
      (node (ref "m10") (pin "13") (pinfunction "13_13") (pintype "passive"))
    )
  )
)
